# motorboard_r2.net
KiCad netlist of a schematic drawn in EAGLE
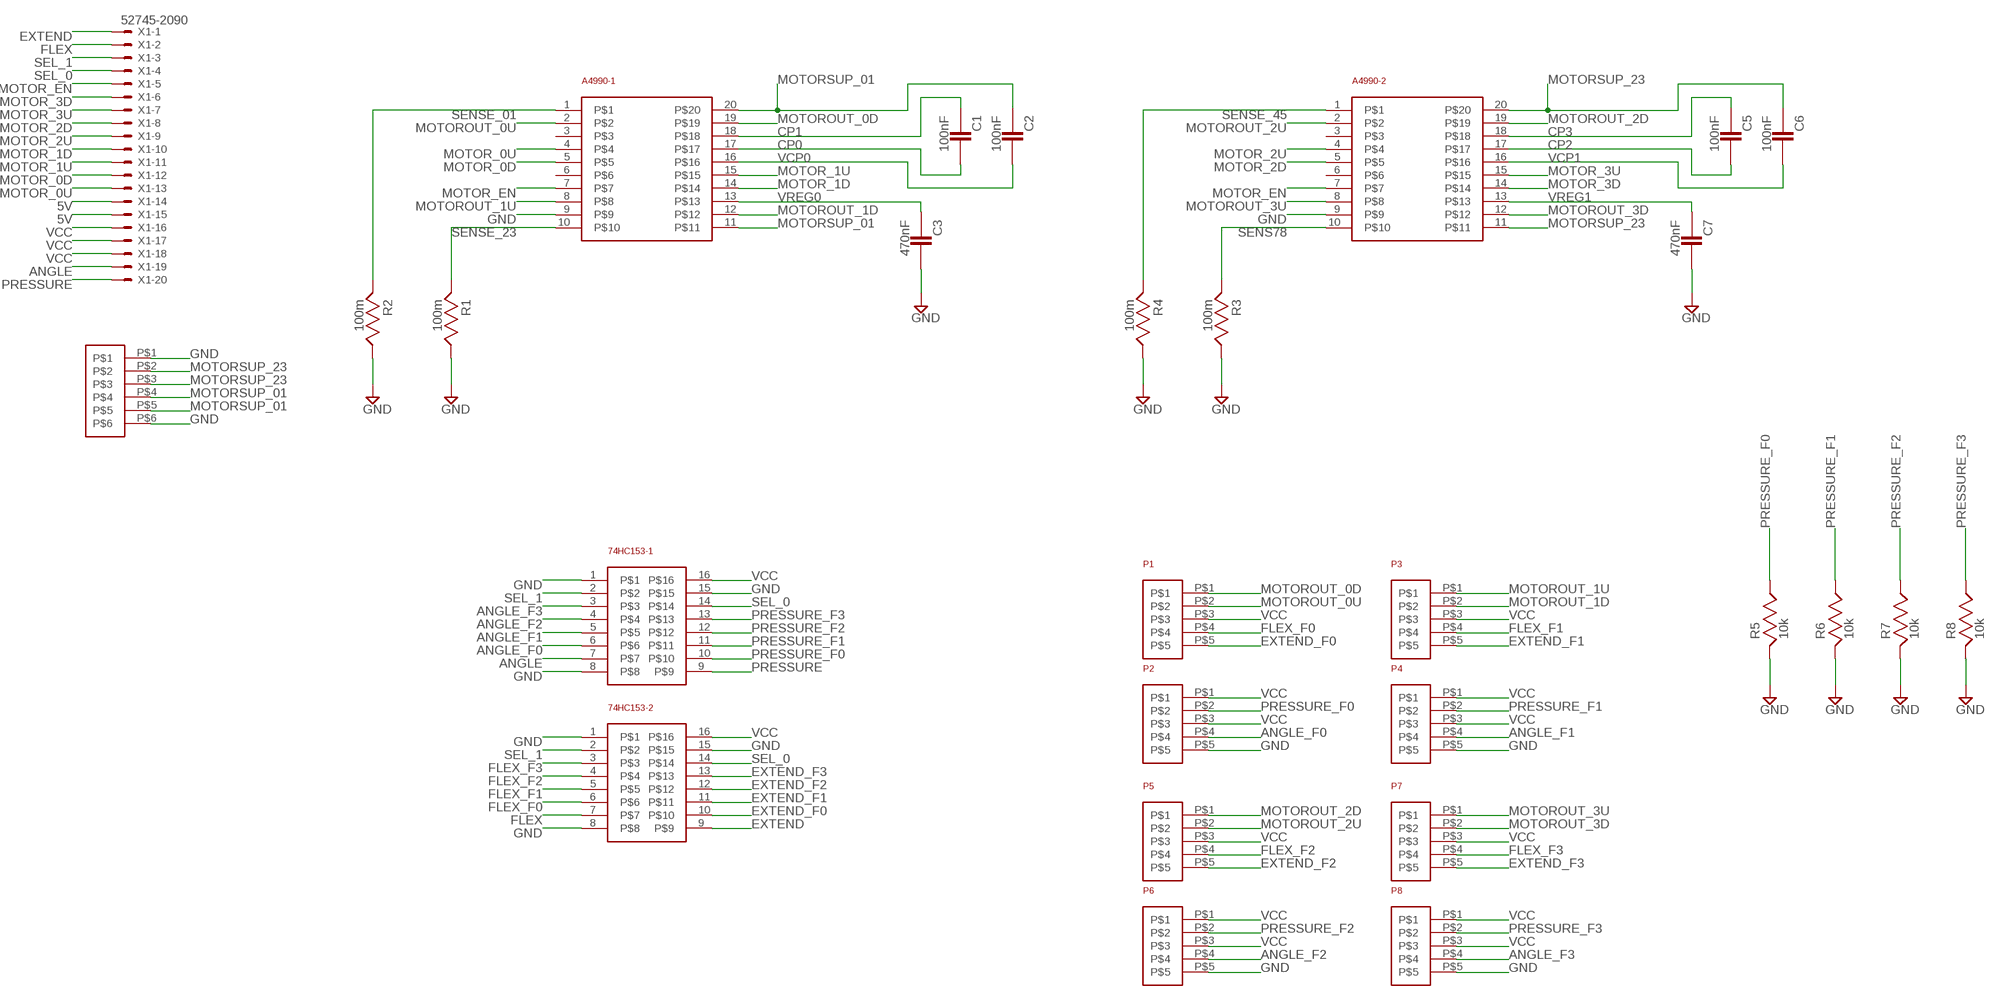
[diagram p0: schematic, sheet 1]

(export (version "E")
  (design (tool "Eeschema 10.0.6"))
  (components
    (comp (ref "74HC153-1")
      (value "74HC153")
      (footprint "eagle-import:SO-16_S-M")
      (libsource (lib "eagle-import") (part "74HC153"))
    )
    (comp (ref "74HC153-2")
      (value "74HC153")
      (footprint "eagle-import:SO-16_S-M")
      (libsource (lib "eagle-import") (part "74HC153"))
    )
    (comp (ref "A4990-1")
      (value "A4990")
      (footprint "eagle-import:A4990")
      (libsource (lib "eagle-import") (part "A4990"))
    )
    (comp (ref "A4990-2")
      (value "A4990")
      (footprint "eagle-import:A4990")
      (libsource (lib "eagle-import") (part "A4990"))
    )
    (comp (ref "C1")
      (value "100nF")
      (footprint "eagle-import:CC0603KRX7R9BB104_CAPC1608X90")
      (fields (field (name "MANUFACTURER") "YAGEO"))
      (libsource (lib "eagle-import") (part "CC0603KRX7R9BB104"))
    )
    (comp (ref "C2")
      (value "100nF")
      (footprint "eagle-import:CC0603KRX7R9BB104_CAPC1608X90")
      (fields (field (name "MANUFACTURER") "YAGEO"))
      (libsource (lib "eagle-import") (part "CC0603KRX7R9BB104"))
    )
    (comp (ref "C3")
      (value "470nF")
      (footprint "eagle-import:CC0603KRX7R9BB104_CAPC1608X90")
      (fields (field (name "MANUFACTURER") "YAGEO"))
      (libsource (lib "eagle-import") (part "CC0603KRX7R9BB104"))
    )
    (comp (ref "C5")
      (value "100nF")
      (footprint "eagle-import:CC0603KRX7R9BB104_CAPC1608X90")
      (fields (field (name "MANUFACTURER") "YAGEO"))
      (libsource (lib "eagle-import") (part "CC0603KRX7R9BB104"))
    )
    (comp (ref "C6")
      (value "100nF")
      (footprint "eagle-import:CC0603KRX7R9BB104_CAPC1608X90")
      (fields (field (name "MANUFACTURER") "YAGEO"))
      (libsource (lib "eagle-import") (part "CC0603KRX7R9BB104"))
    )
    (comp (ref "C7")
      (value "470nF")
      (footprint "eagle-import:CC0603KRX7R9BB104_CAPC1608X90")
      (fields (field (name "MANUFACTURER") "YAGEO"))
      (libsource (lib "eagle-import") (part "CC0603KRX7R9BB104"))
    )
    (comp (ref "P1")
      (value "S5B-PH-SM4-TB")
      (footprint "eagle-import:S5B-PH-SM4-TB")
      (libsource (lib "eagle-import") (part "S5B-PH-SM4-TB"))
    )
    (comp (ref "P2")
      (value "S5B-PH-SM4-TB")
      (footprint "eagle-import:S5B-PH-SM4-TB")
      (libsource (lib "eagle-import") (part "S5B-PH-SM4-TB"))
    )
    (comp (ref "P3")
      (value "S5B-PH-SM4-TB")
      (footprint "eagle-import:S5B-PH-SM4-TB")
      (libsource (lib "eagle-import") (part "S5B-PH-SM4-TB"))
    )
    (comp (ref "P4")
      (value "S5B-PH-SM4-TB")
      (footprint "eagle-import:S5B-PH-SM4-TB")
      (libsource (lib "eagle-import") (part "S5B-PH-SM4-TB"))
    )
    (comp (ref "P5")
      (value "S5B-PH-SM4-TB")
      (footprint "eagle-import:S5B-PH-SM4-TB")
      (libsource (lib "eagle-import") (part "S5B-PH-SM4-TB"))
    )
    (comp (ref "P6")
      (value "S5B-PH-SM4-TB")
      (footprint "eagle-import:S5B-PH-SM4-TB")
      (libsource (lib "eagle-import") (part "S5B-PH-SM4-TB"))
    )
    (comp (ref "P7")
      (value "S5B-PH-SM4-TB")
      (footprint "eagle-import:S5B-PH-SM4-TB")
      (libsource (lib "eagle-import") (part "S5B-PH-SM4-TB"))
    )
    (comp (ref "P8")
      (value "S5B-PH-SM4-TB")
      (footprint "eagle-import:S5B-PH-SM4-TB")
      (libsource (lib "eagle-import") (part "S5B-PH-SM4-TB"))
    )
    (comp (ref "R1")
      (value "100m")
      (footprint "eagle-import:CRCW06031K00FKEA_RESC1608X55")
      (fields (field (name "MANUFACTURER") "VISHAY"))
      (libsource (lib "eagle-import") (part "CRCW06031K00FKEA"))
    )
    (comp (ref "R2")
      (value "100m")
      (footprint "eagle-import:CRCW06031K00FKEA_RESC1608X55")
      (fields (field (name "MANUFACTURER") "VISHAY"))
      (libsource (lib "eagle-import") (part "CRCW06031K00FKEA"))
    )
    (comp (ref "R3")
      (value "100m")
      (footprint "eagle-import:CRCW06031K00FKEA_RESC1608X55")
      (fields (field (name "MANUFACTURER") "VISHAY"))
      (libsource (lib "eagle-import") (part "CRCW06031K00FKEA"))
    )
    (comp (ref "R4")
      (value "100m")
      (footprint "eagle-import:CRCW06031K00FKEA_RESC1608X55")
      (fields (field (name "MANUFACTURER") "VISHAY"))
      (libsource (lib "eagle-import") (part "CRCW06031K00FKEA"))
    )
    (comp (ref "R5")
      (value "10k")
      (footprint "eagle-import:CRCW06031K00FKEA_RESC1608X55")
      (fields (field (name "MANUFACTURER") "VISHAY"))
      (libsource (lib "eagle-import") (part "CRCW06031K00FKEA"))
    )
    (comp (ref "R6")
      (value "10k")
      (footprint "eagle-import:CRCW06031K00FKEA_RESC1608X55")
      (fields (field (name "MANUFACTURER") "VISHAY"))
      (libsource (lib "eagle-import") (part "CRCW06031K00FKEA"))
    )
    (comp (ref "R7")
      (value "10k")
      (footprint "eagle-import:CRCW06031K00FKEA_RESC1608X55")
      (fields (field (name "MANUFACTURER") "VISHAY"))
      (libsource (lib "eagle-import") (part "CRCW06031K00FKEA"))
    )
    (comp (ref "R8")
      (value "10k")
      (footprint "eagle-import:CRCW06031K00FKEA_RESC1608X55")
      (fields (field (name "MANUFACTURER") "VISHAY"))
      (libsource (lib "eagle-import") (part "CRCW06031K00FKEA"))
    )
    (comp (ref "U$1")
      (value "PH-SM4-6")
      (footprint "eagle-import:PH-SM4-6")
      (libsource (lib "eagle-import") (part "PH-SM4-6"))
    )
    (comp (ref "X1")
      (value "52745-2090")
      (footprint "eagle-import:52745-2090")
      (fields (field (name "MF") "WALDOM/MOLEX"))
      (libsource (lib "eagle-import") (part "52745-2090"))
    )
  )
  (nets
    (net (code "1") (name "/5V") (class "Default")
      (node (ref "X1") (pin "14") (pinfunction "S_14") (pintype "passive"))
      (node (ref "X1") (pin "15") (pinfunction "S_15") (pintype "passive"))
    )
    (net (code "2") (name "/ANGLE") (class "Default")
      (node (ref "74HC153-1") (pin "7") (pinfunction "P$7_7") (pintype "bidirectional"))
      (node (ref "X1") (pin "19") (pinfunction "S_19") (pintype "passive"))
    )
    (net (code "3") (name "/ANGLE_F0") (class "Default")
      (node (ref "74HC153-1") (pin "6") (pinfunction "P$6_6") (pintype "bidirectional"))
      (node (ref "P2") (pin "P$4") (pinfunction "P$4_P$4") (pintype "bidirectional"))
    )
    (net (code "4") (name "/ANGLE_F1") (class "Default")
      (node (ref "74HC153-1") (pin "5") (pinfunction "P$5_5") (pintype "bidirectional"))
      (node (ref "P4") (pin "P$4") (pinfunction "P$4_P$4") (pintype "bidirectional"))
    )
    (net (code "5") (name "/ANGLE_F2") (class "Default")
      (node (ref "74HC153-1") (pin "4") (pinfunction "P$4_4") (pintype "bidirectional"))
      (node (ref "P6") (pin "P$4") (pinfunction "P$4_P$4") (pintype "bidirectional"))
    )
    (net (code "6") (name "/ANGLE_F3") (class "Default")
      (node (ref "74HC153-1") (pin "3") (pinfunction "P$3_3") (pintype "bidirectional"))
      (node (ref "P8") (pin "P$4") (pinfunction "P$4_P$4") (pintype "bidirectional"))
    )
    (net (code "7") (name "/CP0") (class "Default")
      (node (ref "A4990-1") (pin "17") (pinfunction "P$17_17") (pintype "bidirectional"))
      (node (ref "C1") (pin "2") (pinfunction "2_2") (pintype "passive"))
    )
    (net (code "8") (name "/CP1") (class "Default")
      (node (ref "A4990-1") (pin "18") (pinfunction "P$18_18") (pintype "bidirectional"))
      (node (ref "C1") (pin "1") (pinfunction "1_1") (pintype "passive"))
    )
    (net (code "9") (name "/CP2") (class "Default")
      (node (ref "A4990-2") (pin "17") (pinfunction "P$17_17") (pintype "bidirectional"))
      (node (ref "C5") (pin "2") (pinfunction "2_2") (pintype "passive"))
    )
    (net (code "10") (name "/CP3") (class "Default")
      (node (ref "A4990-2") (pin "18") (pinfunction "P$18_18") (pintype "bidirectional"))
      (node (ref "C5") (pin "1") (pinfunction "1_1") (pintype "passive"))
    )
    (net (code "11") (name "/EXTEND") (class "Default")
      (node (ref "74HC153-2") (pin "9") (pinfunction "P$9_9") (pintype "bidirectional"))
      (node (ref "X1") (pin "1") (pinfunction "S_1") (pintype "passive"))
    )
    (net (code "12") (name "/EXTEND_F0") (class "Default")
      (node (ref "74HC153-2") (pin "10") (pinfunction "P$10_10") (pintype "bidirectional"))
      (node (ref "P1") (pin "P$5") (pinfunction "P$5_P$5") (pintype "bidirectional"))
    )
    (net (code "13") (name "/EXTEND_F1") (class "Default")
      (node (ref "74HC153-2") (pin "11") (pinfunction "P$11_11") (pintype "bidirectional"))
      (node (ref "P3") (pin "P$5") (pinfunction "P$5_P$5") (pintype "bidirectional"))
    )
    (net (code "14") (name "/EXTEND_F2") (class "Default")
      (node (ref "74HC153-2") (pin "12") (pinfunction "P$12_12") (pintype "bidirectional"))
      (node (ref "P5") (pin "P$5") (pinfunction "P$5_P$5") (pintype "bidirectional"))
    )
    (net (code "15") (name "/EXTEND_F3") (class "Default")
      (node (ref "74HC153-2") (pin "13") (pinfunction "P$13_13") (pintype "bidirectional"))
      (node (ref "P7") (pin "P$5") (pinfunction "P$5_P$5") (pintype "bidirectional"))
    )
    (net (code "16") (name "/FLEX") (class "Default")
      (node (ref "74HC153-2") (pin "7") (pinfunction "P$7_7") (pintype "bidirectional"))
      (node (ref "X1") (pin "2") (pinfunction "S_2") (pintype "passive"))
    )
    (net (code "17") (name "/FLEX_F0") (class "Default")
      (node (ref "74HC153-2") (pin "6") (pinfunction "P$6_6") (pintype "bidirectional"))
      (node (ref "P1") (pin "P$4") (pinfunction "P$4_P$4") (pintype "bidirectional"))
    )
    (net (code "18") (name "/FLEX_F1") (class "Default")
      (node (ref "74HC153-2") (pin "5") (pinfunction "P$5_5") (pintype "bidirectional"))
      (node (ref "P3") (pin "P$4") (pinfunction "P$4_P$4") (pintype "bidirectional"))
    )
    (net (code "19") (name "/FLEX_F2") (class "Default")
      (node (ref "74HC153-2") (pin "4") (pinfunction "P$4_4") (pintype "bidirectional"))
      (node (ref "P5") (pin "P$4") (pinfunction "P$4_P$4") (pintype "bidirectional"))
    )
    (net (code "20") (name "/FLEX_F3") (class "Default")
      (node (ref "74HC153-2") (pin "3") (pinfunction "P$3_3") (pintype "bidirectional"))
      (node (ref "P7") (pin "P$4") (pinfunction "P$4_P$4") (pintype "bidirectional"))
    )
    (net (code "21") (name "/MOTOROUT_0D") (class "Default")
      (node (ref "A4990-1") (pin "19") (pinfunction "P$19_19") (pintype "bidirectional"))
      (node (ref "P1") (pin "P$1") (pinfunction "P$1_P$1") (pintype "bidirectional"))
    )
    (net (code "22") (name "/MOTOROUT_0U") (class "Default")
      (node (ref "A4990-1") (pin "2") (pinfunction "P$2_2") (pintype "bidirectional"))
      (node (ref "P1") (pin "P$2") (pinfunction "P$2_P$2") (pintype "bidirectional"))
    )
    (net (code "23") (name "/MOTOROUT_1D") (class "Default")
      (node (ref "A4990-1") (pin "12") (pinfunction "P$12_12") (pintype "bidirectional"))
      (node (ref "P3") (pin "P$2") (pinfunction "P$2_P$2") (pintype "bidirectional"))
    )
    (net (code "24") (name "/MOTOROUT_1U") (class "Default")
      (node (ref "A4990-1") (pin "8") (pinfunction "P$8_8") (pintype "bidirectional"))
      (node (ref "P3") (pin "P$1") (pinfunction "P$1_P$1") (pintype "bidirectional"))
    )
    (net (code "25") (name "/MOTOROUT_2D") (class "Default")
      (node (ref "A4990-2") (pin "19") (pinfunction "P$19_19") (pintype "bidirectional"))
      (node (ref "P5") (pin "P$1") (pinfunction "P$1_P$1") (pintype "bidirectional"))
    )
    (net (code "26") (name "/MOTOROUT_2U") (class "Default")
      (node (ref "A4990-2") (pin "2") (pinfunction "P$2_2") (pintype "bidirectional"))
      (node (ref "P5") (pin "P$2") (pinfunction "P$2_P$2") (pintype "bidirectional"))
    )
    (net (code "27") (name "/MOTOROUT_3D") (class "Default")
      (node (ref "A4990-2") (pin "12") (pinfunction "P$12_12") (pintype "bidirectional"))
      (node (ref "P7") (pin "P$2") (pinfunction "P$2_P$2") (pintype "bidirectional"))
    )
    (net (code "28") (name "/MOTOROUT_3U") (class "Default")
      (node (ref "A4990-2") (pin "8") (pinfunction "P$8_8") (pintype "bidirectional"))
      (node (ref "P7") (pin "P$1") (pinfunction "P$1_P$1") (pintype "bidirectional"))
    )
    (net (code "29") (name "/MOTORSUP_01") (class "Default")
      (node (ref "A4990-1") (pin "11") (pinfunction "P$11_11") (pintype "bidirectional"))
      (node (ref "A4990-1") (pin "20") (pinfunction "P$20_20") (pintype "bidirectional"))
      (node (ref "C2") (pin "1") (pinfunction "1_1") (pintype "passive"))
      (node (ref "U$1") (pin "P$4") (pinfunction "P$4_P$4") (pintype "bidirectional"))
      (node (ref "U$1") (pin "P$5") (pinfunction "P$5_P$5") (pintype "bidirectional"))
    )
    (net (code "30") (name "/MOTORSUP_23") (class "Default")
      (node (ref "A4990-2") (pin "11") (pinfunction "P$11_11") (pintype "bidirectional"))
      (node (ref "A4990-2") (pin "20") (pinfunction "P$20_20") (pintype "bidirectional"))
      (node (ref "C6") (pin "1") (pinfunction "1_1") (pintype "passive"))
      (node (ref "U$1") (pin "P$2") (pinfunction "P$2_P$2") (pintype "bidirectional"))
      (node (ref "U$1") (pin "P$3") (pinfunction "P$3_P$3") (pintype "bidirectional"))
    )
    (net (code "31") (name "/MOTOR_0D") (class "Default")
      (node (ref "A4990-1") (pin "5") (pinfunction "P$5_5") (pintype "bidirectional"))
      (node (ref "X1") (pin "12") (pinfunction "S_12") (pintype "passive"))
    )
    (net (code "32") (name "/MOTOR_0U") (class "Default")
      (node (ref "A4990-1") (pin "4") (pinfunction "P$4_4") (pintype "bidirectional"))
      (node (ref "X1") (pin "13") (pinfunction "S_13") (pintype "passive"))
    )
    (net (code "33") (name "/MOTOR_1D") (class "Default")
      (node (ref "A4990-1") (pin "14") (pinfunction "P$14_14") (pintype "bidirectional"))
      (node (ref "X1") (pin "10") (pinfunction "S_10") (pintype "passive"))
    )
    (net (code "34") (name "/MOTOR_1U") (class "Default")
      (node (ref "A4990-1") (pin "15") (pinfunction "P$15_15") (pintype "bidirectional"))
      (node (ref "X1") (pin "11") (pinfunction "S_11") (pintype "passive"))
    )
    (net (code "35") (name "/MOTOR_2D") (class "Default")
      (node (ref "A4990-2") (pin "5") (pinfunction "P$5_5") (pintype "bidirectional"))
      (node (ref "X1") (pin "8") (pinfunction "S_8") (pintype "passive"))
    )
    (net (code "36") (name "/MOTOR_2U") (class "Default")
      (node (ref "A4990-2") (pin "4") (pinfunction "P$4_4") (pintype "bidirectional"))
      (node (ref "X1") (pin "9") (pinfunction "S_9") (pintype "passive"))
    )
    (net (code "37") (name "/MOTOR_3D") (class "Default")
      (node (ref "A4990-2") (pin "14") (pinfunction "P$14_14") (pintype "bidirectional"))
      (node (ref "X1") (pin "6") (pinfunction "S_6") (pintype "passive"))
    )
    (net (code "38") (name "/MOTOR_3U") (class "Default")
      (node (ref "A4990-2") (pin "15") (pinfunction "P$15_15") (pintype "bidirectional"))
      (node (ref "X1") (pin "7") (pinfunction "S_7") (pintype "passive"))
    )
    (net (code "39") (name "/MOTOR_EN") (class "Default")
      (node (ref "A4990-1") (pin "7") (pinfunction "P$7_7") (pintype "bidirectional"))
      (node (ref "A4990-2") (pin "7") (pinfunction "P$7_7") (pintype "bidirectional"))
      (node (ref "X1") (pin "5") (pinfunction "S_5") (pintype "passive"))
    )
    (net (code "40") (name "/PRESSURE") (class "Default")
      (node (ref "74HC153-1") (pin "9") (pinfunction "P$9_9") (pintype "bidirectional"))
      (node (ref "X1") (pin "20") (pinfunction "S_20") (pintype "passive"))
    )
    (net (code "41") (name "/PRESSURE_F0") (class "Default")
      (node (ref "74HC153-1") (pin "10") (pinfunction "P$10_10") (pintype "bidirectional"))
      (node (ref "P2") (pin "P$2") (pinfunction "P$2_P$2") (pintype "bidirectional"))
      (node (ref "R5") (pin "2") (pinfunction "2_2") (pintype "passive"))
    )
    (net (code "42") (name "/PRESSURE_F1") (class "Default")
      (node (ref "74HC153-1") (pin "11") (pinfunction "P$11_11") (pintype "bidirectional"))
      (node (ref "P4") (pin "P$2") (pinfunction "P$2_P$2") (pintype "bidirectional"))
      (node (ref "R6") (pin "2") (pinfunction "2_2") (pintype "passive"))
    )
    (net (code "43") (name "/PRESSURE_F2") (class "Default")
      (node (ref "74HC153-1") (pin "12") (pinfunction "P$12_12") (pintype "bidirectional"))
      (node (ref "P6") (pin "P$2") (pinfunction "P$2_P$2") (pintype "bidirectional"))
      (node (ref "R7") (pin "2") (pinfunction "2_2") (pintype "passive"))
    )
    (net (code "44") (name "/PRESSURE_F3") (class "Default")
      (node (ref "74HC153-1") (pin "13") (pinfunction "P$13_13") (pintype "bidirectional"))
      (node (ref "P8") (pin "P$2") (pinfunction "P$2_P$2") (pintype "bidirectional"))
      (node (ref "R8") (pin "2") (pinfunction "2_2") (pintype "passive"))
    )
    (net (code "45") (name "/SEL_0") (class "Default")
      (node (ref "74HC153-1") (pin "14") (pinfunction "P$14_14") (pintype "bidirectional"))
      (node (ref "74HC153-2") (pin "14") (pinfunction "P$14_14") (pintype "bidirectional"))
      (node (ref "X1") (pin "4") (pinfunction "S_4") (pintype "passive"))
    )
    (net (code "46") (name "/SEL_1") (class "Default")
      (node (ref "74HC153-1") (pin "2") (pinfunction "P$2_2") (pintype "bidirectional"))
      (node (ref "74HC153-2") (pin "2") (pinfunction "P$2_2") (pintype "bidirectional"))
      (node (ref "X1") (pin "3") (pinfunction "S_3") (pintype "passive"))
    )
    (net (code "47") (name "/SENS78") (class "Default")
      (node (ref "A4990-2") (pin "10") (pinfunction "P$10_10") (pintype "bidirectional"))
      (node (ref "R3") (pin "1") (pinfunction "1_1") (pintype "passive"))
    )
    (net (code "48") (name "/SENSE_01") (class "Default")
      (node (ref "A4990-1") (pin "1") (pinfunction "P$1_1") (pintype "bidirectional"))
      (node (ref "R2") (pin "1") (pinfunction "1_1") (pintype "passive"))
    )
    (net (code "49") (name "/SENSE_23") (class "Default")
      (node (ref "A4990-1") (pin "10") (pinfunction "P$10_10") (pintype "bidirectional"))
      (node (ref "R1") (pin "1") (pinfunction "1_1") (pintype "passive"))
    )
    (net (code "50") (name "/SENSE_45") (class "Default")
      (node (ref "A4990-2") (pin "1") (pinfunction "P$1_1") (pintype "bidirectional"))
      (node (ref "R4") (pin "1") (pinfunction "1_1") (pintype "passive"))
    )
    (net (code "51") (name "/VCC") (class "Default")
      (node (ref "74HC153-1") (pin "16") (pinfunction "P$16_16") (pintype "bidirectional"))
      (node (ref "74HC153-2") (pin "16") (pinfunction "P$16_16") (pintype "bidirectional"))
      (node (ref "P1") (pin "P$3") (pinfunction "P$3_P$3") (pintype "bidirectional"))
      (node (ref "P2") (pin "P$1") (pinfunction "P$1_P$1") (pintype "bidirectional"))
      (node (ref "P2") (pin "P$3") (pinfunction "P$3_P$3") (pintype "bidirectional"))
      (node (ref "P3") (pin "P$3") (pinfunction "P$3_P$3") (pintype "bidirectional"))
      (node (ref "P4") (pin "P$1") (pinfunction "P$1_P$1") (pintype "bidirectional"))
      (node (ref "P4") (pin "P$3") (pinfunction "P$3_P$3") (pintype "bidirectional"))
      (node (ref "P5") (pin "P$3") (pinfunction "P$3_P$3") (pintype "bidirectional"))
      (node (ref "P6") (pin "P$1") (pinfunction "P$1_P$1") (pintype "bidirectional"))
      (node (ref "P6") (pin "P$3") (pinfunction "P$3_P$3") (pintype "bidirectional"))
      (node (ref "P7") (pin "P$3") (pinfunction "P$3_P$3") (pintype "bidirectional"))
      (node (ref "P8") (pin "P$1") (pinfunction "P$1_P$1") (pintype "bidirectional"))
      (node (ref "P8") (pin "P$3") (pinfunction "P$3_P$3") (pintype "bidirectional"))
      (node (ref "X1") (pin "16") (pinfunction "S_16") (pintype "passive"))
      (node (ref "X1") (pin "17") (pinfunction "S_17") (pintype "passive"))
      (node (ref "X1") (pin "18") (pinfunction "S_18") (pintype "passive"))
    )
    (net (code "52") (name "/VCP0") (class "Default")
      (node (ref "A4990-1") (pin "16") (pinfunction "P$16_16") (pintype "bidirectional"))
      (node (ref "C2") (pin "2") (pinfunction "2_2") (pintype "passive"))
    )
    (net (code "53") (name "/VCP1") (class "Default")
      (node (ref "A4990-2") (pin "16") (pinfunction "P$16_16") (pintype "bidirectional"))
      (node (ref "C6") (pin "2") (pinfunction "2_2") (pintype "passive"))
    )
    (net (code "54") (name "/VREG0") (class "Default")
      (node (ref "A4990-1") (pin "13") (pinfunction "P$13_13") (pintype "bidirectional"))
      (node (ref "C3") (pin "1") (pinfunction "1_1") (pintype "passive"))
    )
    (net (code "55") (name "/VREG1") (class "Default")
      (node (ref "A4990-2") (pin "13") (pinfunction "P$13_13") (pintype "bidirectional"))
      (node (ref "C7") (pin "1") (pinfunction "1_1") (pintype "passive"))
    )
    (net (code "56") (name "GND") (class "Default")
      (node (ref "74HC153-1") (pin "1") (pinfunction "P$1_1") (pintype "bidirectional"))
      (node (ref "74HC153-1") (pin "15") (pinfunction "P$15_15") (pintype "bidirectional"))
      (node (ref "74HC153-1") (pin "8") (pinfunction "P$8_8") (pintype "bidirectional"))
      (node (ref "74HC153-2") (pin "1") (pinfunction "P$1_1") (pintype "bidirectional"))
      (node (ref "74HC153-2") (pin "15") (pinfunction "P$15_15") (pintype "bidirectional"))
      (node (ref "74HC153-2") (pin "8") (pinfunction "P$8_8") (pintype "bidirectional"))
      (node (ref "A4990-1") (pin "9") (pinfunction "P$9_9") (pintype "bidirectional"))
      (node (ref "A4990-2") (pin "9") (pinfunction "P$9_9") (pintype "bidirectional"))
      (node (ref "C3") (pin "2") (pinfunction "2_2") (pintype "passive"))
      (node (ref "C7") (pin "2") (pinfunction "2_2") (pintype "passive"))
      (node (ref "P2") (pin "P$5") (pinfunction "P$5_P$5") (pintype "bidirectional"))
      (node (ref "P4") (pin "P$5") (pinfunction "P$5_P$5") (pintype "bidirectional"))
      (node (ref "P6") (pin "P$5") (pinfunction "P$5_P$5") (pintype "bidirectional"))
      (node (ref "P8") (pin "P$5") (pinfunction "P$5_P$5") (pintype "bidirectional"))
      (node (ref "R1") (pin "2") (pinfunction "2_2") (pintype "passive"))
      (node (ref "R2") (pin "2") (pinfunction "2_2") (pintype "passive"))
      (node (ref "R3") (pin "2") (pinfunction "2_2") (pintype "passive"))
      (node (ref "R4") (pin "2") (pinfunction "2_2") (pintype "passive"))
      (node (ref "R5") (pin "1") (pinfunction "1_1") (pintype "passive"))
      (node (ref "R6") (pin "1") (pinfunction "1_1") (pintype "passive"))
      (node (ref "R7") (pin "1") (pinfunction "1_1") (pintype "passive"))
      (node (ref "R8") (pin "1") (pinfunction "1_1") (pintype "passive"))
      (node (ref "U$1") (pin "P$1") (pinfunction "P$1_P$1") (pintype "bidirectional"))
      (node (ref "U$1") (pin "P$6") (pinfunction "P$6_P$6") (pintype "bidirectional"))
    )
    (net (code "57") (name "unconnected-(A4990-1-P$3-Pad3)") (class "Default")
      (node (ref "A4990-1") (pin "3") (pinfunction "P$3_3") (pintype "bidirectional"))
    )
    (net (code "58") (name "unconnected-(A4990-1-P$6-Pad6)") (class "Default")
      (node (ref "A4990-1") (pin "6") (pinfunction "P$6_6") (pintype "bidirectional"))
    )
    (net (code "59") (name "unconnected-(A4990-2-P$3-Pad3)") (class "Default")
      (node (ref "A4990-2") (pin "3") (pinfunction "P$3_3") (pintype "bidirectional"))
    )
    (net (code "60") (name "unconnected-(A4990-2-P$6-Pad6)") (class "Default")
      (node (ref "A4990-2") (pin "6") (pinfunction "P$6_6") (pintype "bidirectional"))
    )
  )
)
